# ST25DV64K-JFR6D3.net
KiCad netlist of a schematic drawn in Altium Designer
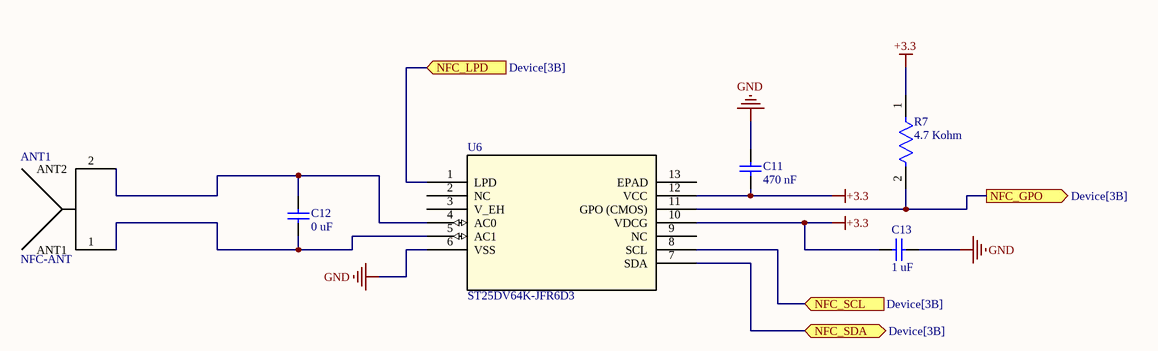
[diagram p0: ST25DV64K-JFR6D3.SchDoc]

(export (version "E")
  (design (tool "Eeschema 10.0.6"))
  (components
    (comp (ref "ANT1") (value "NFC-ANT") (footprint "NFC-ANT") (libsource (lib "Custom.") (part "NFC-ANT")))
    (comp (ref "C11")
      (value "470 nF")
      (footprint "CAPC1005X55X25NL05T10")
      (fields (field (name "MANUFACTURER") "Murata") (field (name "PART NUMBER") "GRM155F50J684ZE01D"))
      (libsource (lib "Altium Content Vault") (part "CAP"))
    )
    (comp (ref "C12")
      (value "0 uF")
      (footprint "CAPC1005X55X25NL05T10")
      (fields (field (name "MANUFACTURER") "Murata") (field (name "PART NUMBER") "GRM155F50J684ZE01D"))
      (libsource (lib "Altium Content Vault") (part "CAP"))
    )
    (comp (ref "C13")
      (value "1 uF")
      (footprint "CAPC1005X55X25NL05T10")
      (fields (field (name "MANUFACTURER") "Murata") (field (name "PART NUMBER") "GRM155F50J684ZE01D"))
      (libsource (lib "Altium Content Vault") (part "CAP"))
    )
    (comp (ref "R7")
      (value "4.7 Kohm")
      (footprint "FP-RC1005-IPC_C")
      (description "Res Thick Film 0402 1.87kΩ 1% 0.063W ±100ppm/°C Molded SMD T/R")
      (fields (field (name "TOLERANCE") "1%"))
      (libsource (lib "Altium Content Vault") (part "1029c3af85768c4190bb7ad29bc67b5"))
    )
    (comp (ref "U6")
      (value "ST25DV64K-JFR6D3")
      (footprint "ST25DV64K-JFR6D3")
      (libsource (lib "ReadyButNotListed") (part "ST25DV64K-JFR6D3"))
    )
  )
  (nets
    (net (code "1") (name "+3.3") (class "Default")
      (node (ref "C11") (pin "2") (pinfunction "2_2") (pintype "passive"))
      (node (ref "C13") (pin "1") (pinfunction "1_1") (pintype "passive"))
      (node (ref "R7") (pin "1") (pinfunction "1_1") (pintype "passive"))
      (node (ref "U6") (pin "10") (pinfunction "VDCG_10") (pintype "passive"))
      (node (ref "U6") (pin "12") (pinfunction "VCC_12") (pintype "power_in"))
    )
    (net (code "2") (name "/NFC_GPO") (class "Default")
      (node (ref "R7") (pin "2") (pinfunction "2_2") (pintype "passive"))
      (node (ref "U6") (pin "11") (pinfunction "GPO_(CMOS)_11") (pintype "passive"))
    )
    (net (code "3") (name "/NFC_LPD") (class "Default")
      (node (ref "U6") (pin "1") (pinfunction "LPD_1") (pintype "passive"))
    )
    (net (code "4") (name "/NFC_SCL") (class "Default")
      (node (ref "U6") (pin "8") (pinfunction "SCL_8") (pintype "passive"))
    )
    (net (code "5") (name "/NFC_SDA") (class "Default")
      (node (ref "U6") (pin "7") (pinfunction "SDA_7") (pintype "passive"))
    )
    (net (code "6") (name "GND") (class "Default")
      (node (ref "C11") (pin "1") (pinfunction "1_1") (pintype "passive"))
      (node (ref "C13") (pin "2") (pinfunction "2_2") (pintype "passive"))
      (node (ref "U6") (pin "6") (pinfunction "VSS_6") (pintype "passive"))
    )
    (net (code "7") (name "Net-(ANT1-ANT1)") (class "Default")
      (node (ref "ANT1") (pin "1") (pinfunction "ANT1_1") (pintype "passive"))
      (node (ref "C12") (pin "2") (pinfunction "2_2") (pintype "passive"))
      (node (ref "U6") (pin "5") (pinfunction "AC1_5") (pintype "bidirectional"))
    )
    (net (code "8") (name "Net-(ANT1-ANT2)") (class "Default")
      (node (ref "ANT1") (pin "2") (pinfunction "ANT2_2") (pintype "passive"))
      (node (ref "C12") (pin "1") (pinfunction "1_1") (pintype "passive"))
      (node (ref "U6") (pin "4") (pinfunction "AC0_4") (pintype "bidirectional"))
    )
    (net (code "9") (name "unconnected-(U6-EPAD-Pad13)") (class "Default")
      (node (ref "U6") (pin "13") (pinfunction "EPAD_13") (pintype "passive"))
    )
    (net (code "10") (name "unconnected-(U6-NC-Pad2)") (class "Default")
      (node (ref "U6") (pin "2") (pinfunction "NC_2") (pintype "passive"))
    )
    (net (code "11") (name "unconnected-(U6-NC-Pad9)") (class "Default")
      (node (ref "U6") (pin "9") (pinfunction "NC_9") (pintype "passive"))
    )
    (net (code "12") (name "unconnected-(U6-V_EH-Pad3)") (class "Default")
      (node (ref "U6") (pin "3") (pinfunction "V_EH_3") (pintype "passive"))
    )
  )
)
